# PowerCapV2.net
KiCad netlist of a schematic drawn in EAGLE
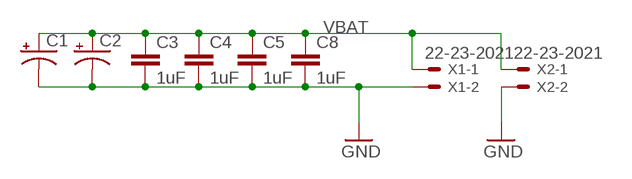
[diagram p0: schematic, sheet 1]

(export (version "E")
  (design (tool "Eeschema 10.0.6"))
  (components
    (comp (ref "C1")
      (value "CAP_POLPTH4")
      (footprint "eagle-import:CPOL-RADIAL-1000UF-25V")
      (libsource (lib "eagle-import") (part "CAP_POLPTH4"))
    )
    (comp (ref "C2")
      (value "CAP_POLPTH4")
      (footprint "eagle-import:CPOL-RADIAL-1000UF-25V")
      (libsource (lib "eagle-import") (part "CAP_POLPTH4"))
    )
    (comp (ref "C3")
      (value "1uF")
      (footprint "eagle-import:0805-CAP")
      (libsource (lib "eagle-import") (part "1UF-25V-10%(0805){dblquote}"))
    )
    (comp (ref "C4")
      (value "1uF")
      (footprint "eagle-import:0805-CAP")
      (libsource (lib "eagle-import") (part "1UF-25V-10%(0805){dblquote}"))
    )
    (comp (ref "C5")
      (value "1uF")
      (footprint "eagle-import:0805-CAP")
      (libsource (lib "eagle-import") (part "1UF-25V-10%(0805){dblquote}"))
    )
    (comp (ref "C8")
      (value "1uF")
      (footprint "eagle-import:0805-CAP")
      (libsource (lib "eagle-import") (part "1UF-25V-10%(0805){dblquote}"))
    )
    (comp (ref "X1")
      (value "22-23-2021")
      (footprint "eagle-import:22-23-2021")
      (fields (field (name "MF") "MOLEX"))
      (libsource (lib "eagle-import") (part "22-23-2021"))
    )
    (comp (ref "X2")
      (value "22-23-2021")
      (footprint "eagle-import:22-23-2021")
      (fields (field (name "MF") "MOLEX"))
      (libsource (lib "eagle-import") (part "22-23-2021"))
    )
  )
  (nets
    (net (code "1") (name "/VBAT") (class "Default")
      (node (ref "C1") (pin "+") (pinfunction "+_+") (pintype "passive"))
      (node (ref "C2") (pin "+") (pinfunction "+_+") (pintype "passive"))
      (node (ref "C3") (pin "1") (pinfunction "1_1") (pintype "passive"))
      (node (ref "C4") (pin "1") (pinfunction "1_1") (pintype "passive"))
      (node (ref "C5") (pin "1") (pinfunction "1_1") (pintype "passive"))
      (node (ref "C8") (pin "1") (pinfunction "1_1") (pintype "passive"))
      (node (ref "X1") (pin "1") (pinfunction "S_1") (pintype "passive"))
      (node (ref "X2") (pin "1") (pinfunction "S_1") (pintype "passive"))
    )
    (net (code "2") (name "GND") (class "Default")
      (node (ref "C1") (pin "-") (pinfunction "-_-") (pintype "passive"))
      (node (ref "C2") (pin "-") (pinfunction "-_-") (pintype "passive"))
      (node (ref "C3") (pin "2") (pinfunction "2_2") (pintype "passive"))
      (node (ref "C4") (pin "2") (pinfunction "2_2") (pintype "passive"))
      (node (ref "C5") (pin "2") (pinfunction "2_2") (pintype "passive"))
      (node (ref "C8") (pin "2") (pinfunction "2_2") (pintype "passive"))
      (node (ref "X1") (pin "2") (pinfunction "S_2") (pintype "passive"))
      (node (ref "X2") (pin "2") (pinfunction "S_2") (pintype "passive"))
    )
  )
)
